# PCB_2.net
KiCad netlist of a schematic drawn in EAGLE
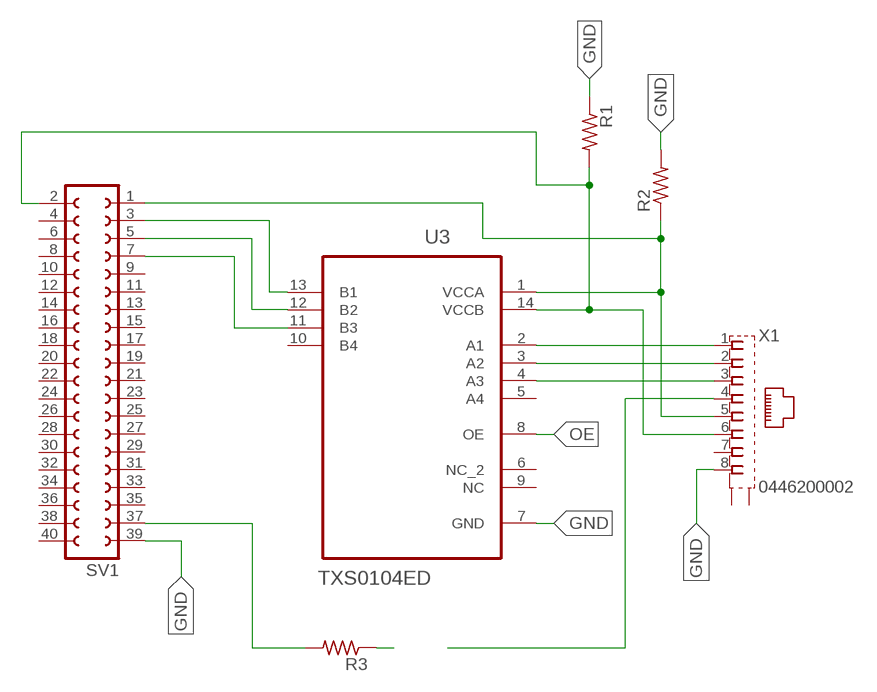
[diagram p0: schematic, sheet 1]

(export (version "E")
  (design (tool "Eeschema 10.0.6"))
  (components
    (comp (ref "R1")
      (value "R-US_R0805")
      (footprint "eagle-import:R0805")
      (libsource (lib "eagle-import") (part "R-US_R0805"))
    )
    (comp (ref "R2")
      (value "R-US_R0805")
      (footprint "eagle-import:R0805")
      (libsource (lib "eagle-import") (part "R-US_R0805"))
    )
    (comp (ref "R3")
      (value "R-US_R0805")
      (footprint "eagle-import:R0805")
      (libsource (lib "eagle-import") (part "R-US_R0805"))
    )
    (comp (ref "SV1")
      (value "FE20-2")
      (footprint "eagle-import:FE20-2")
      (libsource (lib "eagle-import") (part "FE20-2"))
    )
    (comp (ref "U3")
      (value "TXS0104ED")
      (footprint "eagle-import:SOIC127P600X175-14N")
      (fields (field (name "MF") "Texas Instruments"))
      (libsource (lib "eagle-import") (part "TXS0104ED"))
    )
    (comp (ref "X1")
      (value "0446200002")
      (footprint "eagle-import:0446200002")
      (fields (field (name "MF") "Molex, LLC"))
      (libsource (lib "eagle-import") (part "0446200002"))
    )
  )
  (nets
    (net (code "1") (name "GND") (class "Default")
      (node (ref "R1") (pin "1") (pinfunction "1_1") (pintype "passive"))
      (node (ref "R2") (pin "2") (pinfunction "2_2") (pintype "passive"))
      (node (ref "SV1") (pin "39") (pinfunction "39_39") (pintype "passive"))
      (node (ref "U3") (pin "7") (pinfunction "GND_7") (pintype "passive"))
      (node (ref "X1") (pin "8") (pinfunction "8_8") (pintype "passive"))
    )
    (net (code "2") (name "Net-(R3-Pad2)") (class "Default")
      (node (ref "R3") (pin "2") (pinfunction "2_2") (pintype "passive"))
      (node (ref "SV1") (pin "37") (pinfunction "37_37") (pintype "passive"))
    )
    (net (code "3") (name "Net-(U3-A1)") (class "Default")
      (node (ref "U3") (pin "2") (pinfunction "A1_2") (pintype "input"))
      (node (ref "X1") (pin "1") (pinfunction "1_1") (pintype "passive"))
    )
    (net (code "4") (name "Net-(U3-A2)") (class "Default")
      (node (ref "U3") (pin "3") (pinfunction "A2_3") (pintype "input"))
      (node (ref "X1") (pin "2") (pinfunction "2_2") (pintype "passive"))
    )
    (net (code "5") (name "Net-(U3-A3)") (class "Default")
      (node (ref "U3") (pin "4") (pinfunction "A3_4") (pintype "input"))
      (node (ref "X1") (pin "3") (pinfunction "3_3") (pintype "passive"))
    )
    (net (code "6") (name "Net-(U3-B1)") (class "Default")
      (node (ref "SV1") (pin "3") (pinfunction "3_3") (pintype "passive"))
      (node (ref "U3") (pin "13") (pinfunction "B1_13") (pintype "output"))
    )
    (net (code "7") (name "Net-(U3-B2)") (class "Default")
      (node (ref "SV1") (pin "5") (pinfunction "5_5") (pintype "passive"))
      (node (ref "U3") (pin "12") (pinfunction "B2_12") (pintype "output"))
    )
    (net (code "8") (name "Net-(U3-B3)") (class "Default")
      (node (ref "SV1") (pin "7") (pinfunction "7_7") (pintype "passive"))
      (node (ref "U3") (pin "11") (pinfunction "B3_11") (pintype "output"))
    )
    (net (code "9") (name "Net-(U3-VCCA)") (class "Default")
      (node (ref "R2") (pin "1") (pinfunction "1_1") (pintype "passive"))
      (node (ref "SV1") (pin "1") (pinfunction "1_1") (pintype "passive"))
      (node (ref "U3") (pin "1") (pinfunction "VCCA_1") (pintype "power_in"))
      (node (ref "X1") (pin "5") (pinfunction "5_5") (pintype "passive"))
    )
    (net (code "10") (name "Net-(U3-VCCB)") (class "Default")
      (node (ref "R1") (pin "2") (pinfunction "2_2") (pintype "passive"))
      (node (ref "SV1") (pin "2") (pinfunction "2_2") (pintype "passive"))
      (node (ref "U3") (pin "14") (pinfunction "VCCB_14") (pintype "power_in"))
      (node (ref "X1") (pin "6") (pinfunction "6_6") (pintype "passive"))
    )
    (net (code "11") (name "OE") (class "Default")
      (node (ref "U3") (pin "8") (pinfunction "OE_8") (pintype "input"))
    )
    (net (code "12") (name "unconnected-(R3-Pad1)") (class "Default")
      (node (ref "R3") (pin "1") (pinfunction "1_1") (pintype "passive"))
    )
    (net (code "13") (name "unconnected-(SV1-Pad4)") (class "Default")
      (node (ref "SV1") (pin "4") (pinfunction "4_4") (pintype "passive"))
    )
    (net (code "14") (name "unconnected-(SV1-Pad6)") (class "Default")
      (node (ref "SV1") (pin "6") (pinfunction "6_6") (pintype "passive"))
    )
    (net (code "15") (name "unconnected-(SV1-Pad8)") (class "Default")
      (node (ref "SV1") (pin "8") (pinfunction "8_8") (pintype "passive"))
    )
    (net (code "16") (name "unconnected-(SV1-Pad9)") (class "Default")
      (node (ref "SV1") (pin "9") (pinfunction "9_9") (pintype "passive"))
    )
    (net (code "17") (name "unconnected-(SV1-Pad10)") (class "Default")
      (node (ref "SV1") (pin "10") (pinfunction "10_10") (pintype "passive"))
    )
    (net (code "18") (name "unconnected-(SV1-Pad11)") (class "Default")
      (node (ref "SV1") (pin "11") (pinfunction "11_11") (pintype "passive"))
    )
    (net (code "19") (name "unconnected-(SV1-Pad12)") (class "Default")
      (node (ref "SV1") (pin "12") (pinfunction "12_12") (pintype "passive"))
    )
    (net (code "20") (name "unconnected-(SV1-Pad13)") (class "Default")
      (node (ref "SV1") (pin "13") (pinfunction "13_13") (pintype "passive"))
    )
    (net (code "21") (name "unconnected-(SV1-Pad14)") (class "Default")
      (node (ref "SV1") (pin "14") (pinfunction "14_14") (pintype "passive"))
    )
    (net (code "22") (name "unconnected-(SV1-Pad15)") (class "Default")
      (node (ref "SV1") (pin "15") (pinfunction "15_15") (pintype "passive"))
    )
    (net (code "23") (name "unconnected-(SV1-Pad16)") (class "Default")
      (node (ref "SV1") (pin "16") (pinfunction "16_16") (pintype "passive"))
    )
    (net (code "24") (name "unconnected-(SV1-Pad17)") (class "Default")
      (node (ref "SV1") (pin "17") (pinfunction "17_17") (pintype "passive"))
    )
    (net (code "25") (name "unconnected-(SV1-Pad18)") (class "Default")
      (node (ref "SV1") (pin "18") (pinfunction "18_18") (pintype "passive"))
    )
    (net (code "26") (name "unconnected-(SV1-Pad19)") (class "Default")
      (node (ref "SV1") (pin "19") (pinfunction "19_19") (pintype "passive"))
    )
    (net (code "27") (name "unconnected-(SV1-Pad20)") (class "Default")
      (node (ref "SV1") (pin "20") (pinfunction "20_20") (pintype "passive"))
    )
    (net (code "28") (name "unconnected-(SV1-Pad21)") (class "Default")
      (node (ref "SV1") (pin "21") (pinfunction "21_21") (pintype "passive"))
    )
    (net (code "29") (name "unconnected-(SV1-Pad22)") (class "Default")
      (node (ref "SV1") (pin "22") (pinfunction "22_22") (pintype "passive"))
    )
    (net (code "30") (name "unconnected-(SV1-Pad23)") (class "Default")
      (node (ref "SV1") (pin "23") (pinfunction "23_23") (pintype "passive"))
    )
    (net (code "31") (name "unconnected-(SV1-Pad24)") (class "Default")
      (node (ref "SV1") (pin "24") (pinfunction "24_24") (pintype "passive"))
    )
    (net (code "32") (name "unconnected-(SV1-Pad25)") (class "Default")
      (node (ref "SV1") (pin "25") (pinfunction "25_25") (pintype "passive"))
    )
    (net (code "33") (name "unconnected-(SV1-Pad26)") (class "Default")
      (node (ref "SV1") (pin "26") (pinfunction "26_26") (pintype "passive"))
    )
    (net (code "34") (name "unconnected-(SV1-Pad27)") (class "Default")
      (node (ref "SV1") (pin "27") (pinfunction "27_27") (pintype "passive"))
    )
    (net (code "35") (name "unconnected-(SV1-Pad28)") (class "Default")
      (node (ref "SV1") (pin "28") (pinfunction "28_28") (pintype "passive"))
    )
    (net (code "36") (name "unconnected-(SV1-Pad29)") (class "Default")
      (node (ref "SV1") (pin "29") (pinfunction "29_29") (pintype "passive"))
    )
    (net (code "37") (name "unconnected-(SV1-Pad30)") (class "Default")
      (node (ref "SV1") (pin "30") (pinfunction "30_30") (pintype "passive"))
    )
    (net (code "38") (name "unconnected-(SV1-Pad31)") (class "Default")
      (node (ref "SV1") (pin "31") (pinfunction "31_31") (pintype "passive"))
    )
    (net (code "39") (name "unconnected-(SV1-Pad32)") (class "Default")
      (node (ref "SV1") (pin "32") (pinfunction "32_32") (pintype "passive"))
    )
    (net (code "40") (name "unconnected-(SV1-Pad33)") (class "Default")
      (node (ref "SV1") (pin "33") (pinfunction "33_33") (pintype "passive"))
    )
    (net (code "41") (name "unconnected-(SV1-Pad34)") (class "Default")
      (node (ref "SV1") (pin "34") (pinfunction "34_34") (pintype "passive"))
    )
    (net (code "42") (name "unconnected-(SV1-Pad35)") (class "Default")
      (node (ref "SV1") (pin "35") (pinfunction "35_35") (pintype "passive"))
    )
    (net (code "43") (name "unconnected-(SV1-Pad36)") (class "Default")
      (node (ref "SV1") (pin "36") (pinfunction "36_36") (pintype "passive"))
    )
    (net (code "44") (name "unconnected-(SV1-Pad38)") (class "Default")
      (node (ref "SV1") (pin "38") (pinfunction "38_38") (pintype "passive"))
    )
    (net (code "45") (name "unconnected-(SV1-Pad40)") (class "Default")
      (node (ref "SV1") (pin "40") (pinfunction "40_40") (pintype "passive"))
    )
    (net (code "46") (name "unconnected-(U3-A4-Pad5)") (class "Default")
      (node (ref "U3") (pin "5") (pinfunction "A4_5") (pintype "input"))
    )
    (net (code "47") (name "unconnected-(U3-B4-Pad10)") (class "Default")
      (node (ref "U3") (pin "10") (pinfunction "B4_10") (pintype "output"))
    )
    (net (code "48") (name "unconnected-(U3-NC-Pad9)") (class "Default")
      (node (ref "U3") (pin "9") (pinfunction "NC_9") (pintype "no_connect"))
    )
    (net (code "49") (name "unconnected-(U3-NC_2-Pad6)") (class "Default")
      (node (ref "U3") (pin "6") (pinfunction "NC_2_6") (pintype "no_connect"))
    )
    (net (code "50") (name "unconnected-(X1-Pad4)") (class "Default")
      (node (ref "X1") (pin "4") (pinfunction "4_4") (pintype "passive"))
    )
    (net (code "51") (name "unconnected-(X1-Pad7)") (class "Default")
      (node (ref "X1") (pin "7") (pinfunction "7_7") (pintype "passive"))
    )
    (net (code "52") (name "unconnected-(X1-S1-PadS@1)") (class "Default")
      (node (ref "X1") (pin "S@1") (pinfunction "S1_S@1") (pintype "passive"))
    )
    (net (code "53") (name "unconnected-(X1-S2-PadS@2)") (class "Default")
      (node (ref "X1") (pin "S@2") (pinfunction "S2_S@2") (pintype "passive"))
    )
  )
)
